# 06_USB_HOST.net
KiCad netlist of a schematic drawn in Altium Designer
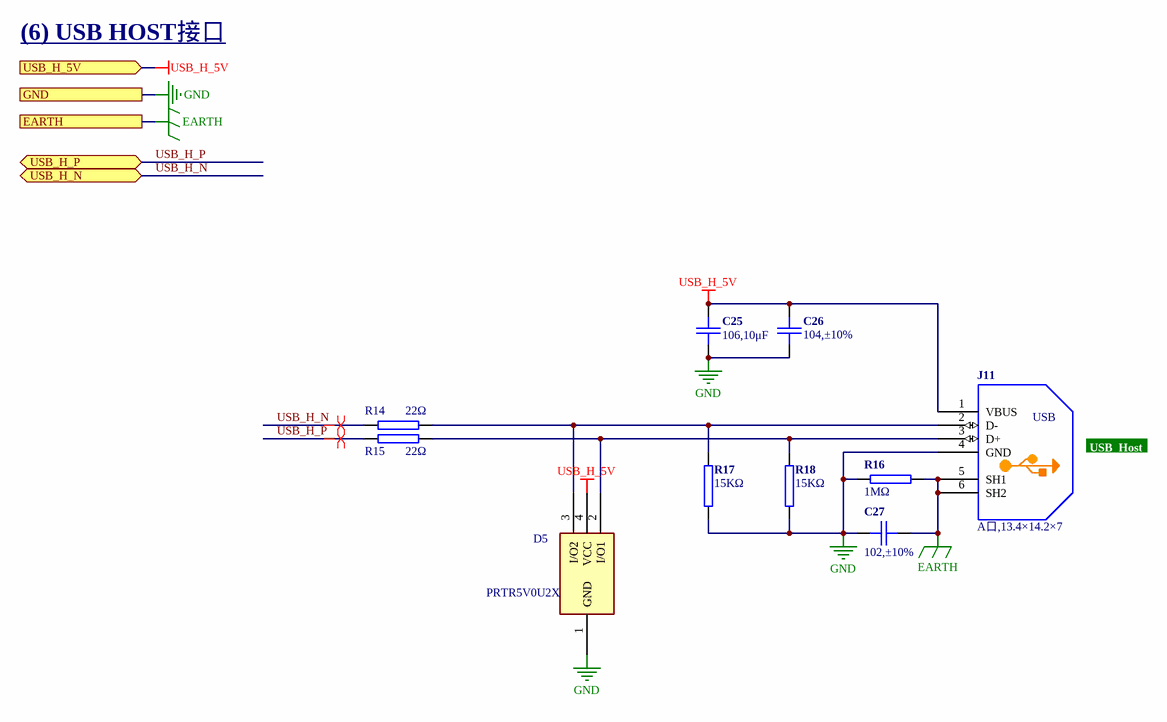
[diagram p0: 06. USB HOST.SchDoc]

(export (version "E")
  (design (tool "Eeschema 10.0.6"))
  (components
    (comp (ref "C25")
      (value "106,10μF")
      (footprint "0805C")
      (description "Capacitor")
      (libsource (lib "ErpMaterialData") (part "CAP1"))
    )
    (comp (ref "C26")
      (value "104,±10%")
      (footprint "0603C")
      (description "Capacitor")
      (libsource (lib "ErpMaterialData") (part "CAP1"))
    )
    (comp (ref "C27")
      (value "102,±10%")
      (footprint "1206C")
      (description "Capacitor")
      (libsource (lib "ErpMaterialData") (part "CAP1"))
    )
    (comp (ref "D5")
      (value "PRTR5V0U2X")
      (footprint "SOT-143")
      (description "PRTR5V0U2X,SOT-143B,NXP,RoHS")
      (libsource (lib "ErpMaterialData") (part "PRTR5V0U2X"))
    )
    (comp (ref "J11")
      (value "A口,13.4×14.2×7")
      (footprint "USB-A")
      (description "A口,13.4×14.2×7,90°,RoHS")
      (fields (field (name "Comment") "USB"))
      (libsource (lib "ErpMaterialData") (part "USB1"))
    )
    (comp (ref "R14") (value "22Ω") (footprint "0603R") (libsource (lib "ErpMaterialData") (part "RES2")))
    (comp (ref "R15") (value "22Ω") (footprint "0603R") (libsource (lib "ErpMaterialData") (part "RES2")))
    (comp (ref "R16") (value "1MΩ") (footprint "1206R") (libsource (lib "ErpMaterialData") (part "RES2")))
    (comp (ref "R17") (value "15KΩ") (footprint "0603R") (libsource (lib "ErpMaterialData") (part "RES2")))
    (comp (ref "R18") (value "15KΩ") (footprint "0603R") (libsource (lib "ErpMaterialData") (part "RES2")))
  )
  (nets
    (net (code "1") (name "/USB_H_N") (class "Default")
      (node (ref "R14") (pin "2") (pinfunction "2_2") (pintype "passive"))
    )
    (net (code "2") (name "/USB_H_P") (class "Default")
      (node (ref "R15") (pin "2") (pinfunction "2_2") (pintype "passive"))
    )
    (net (code "3") (name "EARTH") (class "Default")
      (node (ref "C27") (pin "2") (pinfunction "2_2") (pintype "passive"))
      (node (ref "J11") (pin "5") (pinfunction "SH1_5") (pintype "passive"))
      (node (ref "J11") (pin "6") (pinfunction "SH2_6") (pintype "passive"))
      (node (ref "R16") (pin "2") (pinfunction "2_2") (pintype "passive"))
    )
    (net (code "4") (name "GND") (class "Default")
      (node (ref "C25") (pin "2") (pinfunction "2_2") (pintype "passive"))
      (node (ref "C26") (pin "2") (pinfunction "2_2") (pintype "passive"))
      (node (ref "C27") (pin "1") (pinfunction "1_1") (pintype "passive"))
      (node (ref "D5") (pin "1") (pinfunction "GND_1") (pintype "passive"))
      (node (ref "J11") (pin "4") (pinfunction "GND_4") (pintype "power_in"))
      (node (ref "R16") (pin "1") (pinfunction "1_1") (pintype "passive"))
      (node (ref "R17") (pin "1") (pinfunction "1_1") (pintype "passive"))
      (node (ref "R18") (pin "1") (pinfunction "1_1") (pintype "passive"))
    )
    (net (code "5") (name "Net-(D5-I{slash}O1)") (class "Default")
      (node (ref "D5") (pin "2") (pinfunction "I/O1_2") (pintype "passive"))
      (node (ref "J11") (pin "3") (pinfunction "D+_3") (pintype "bidirectional"))
      (node (ref "R15") (pin "1") (pinfunction "1_1") (pintype "passive"))
      (node (ref "R18") (pin "2") (pinfunction "2_2") (pintype "passive"))
    )
    (net (code "6") (name "Net-(D5-I{slash}O2)") (class "Default")
      (node (ref "D5") (pin "3") (pinfunction "I/O2_3") (pintype "passive"))
      (node (ref "J11") (pin "2") (pinfunction "D-_2") (pintype "bidirectional"))
      (node (ref "R14") (pin "1") (pinfunction "1_1") (pintype "passive"))
      (node (ref "R17") (pin "2") (pinfunction "2_2") (pintype "passive"))
    )
    (net (code "7") (name "USB_H_5V") (class "Default")
      (node (ref "C25") (pin "1") (pinfunction "1_1") (pintype "passive"))
      (node (ref "C26") (pin "1") (pinfunction "1_1") (pintype "passive"))
      (node (ref "D5") (pin "4") (pinfunction "VCC_4") (pintype "passive"))
      (node (ref "J11") (pin "1") (pinfunction "VBUS_1") (pintype "passive"))
    )
  )
)
